# MB-Arduino-uno.net
KiCad netlist of a schematic drawn in EAGLE
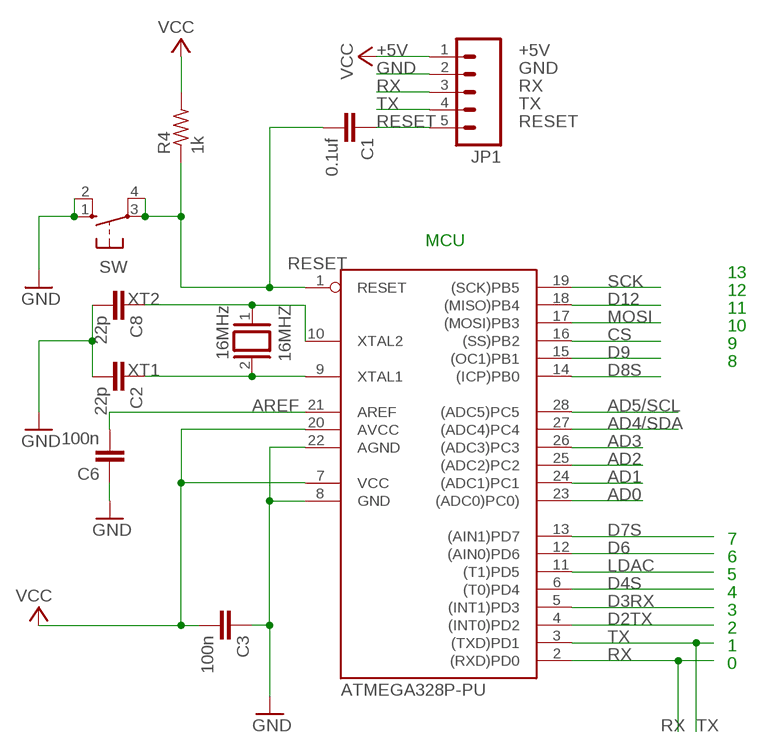
[diagram p0: schematic, sheet 1]

(export (version "E")
  (design (tool "Eeschema 10.0.6"))
  (components
    (comp (ref "16MHZ")
      (value "16MHz")
      (footprint "eagle-import:QS")
      (libsource (lib "eagle-import") (part "XTAL/S"))
    )
    (comp (ref "C1")
      (value "0.1uf")
      (footprint "eagle-import:C2.5-2")
      (libsource (lib "eagle-import") (part "C2.5/2"))
    )
    (comp (ref "C2")
      (value "22p")
      (footprint "eagle-import:C2.5-2")
      (libsource (lib "eagle-import") (part "C2.5/2"))
    )
    (comp (ref "C3")
      (value "100n")
      (footprint "eagle-import:C2.5-2")
      (libsource (lib "eagle-import") (part "C2.5/2"))
    )
    (comp (ref "C6")
      (value "100n")
      (footprint "eagle-import:C2.5-2")
      (libsource (lib "eagle-import") (part "C2.5/2"))
    )
    (comp (ref "C8")
      (value "22p")
      (footprint "eagle-import:C2.5-2")
      (libsource (lib "eagle-import") (part "C2.5/2"))
    )
    (comp (ref "IC")
      (value "ATMEGA328P-PU")
      (footprint "eagle-import:DIL28-3")
      (libsource (lib "eagle-import") (part "ATMEGA328P-PU"))
    )
    (comp (ref "JP1")
      (value "M05PTH")
      (footprint "eagle-import:1X05")
      (libsource (lib "eagle-import") (part "M05PTH"))
    )
    (comp (ref "R4")
      (value "1k")
      (footprint "eagle-import:0204_7")
      (libsource (lib "eagle-import") (part "R-US_0204/7"))
    )
    (comp (ref "SW")
      (value "10-XX")
      (footprint "eagle-import:B3F-10XX")
      (fields (field (name "MPN") "B3F-1000"))
      (libsource (lib "eagle-import") (part "10-XX"))
    )
  )
  (nets
    (net (code "1") (name "/AD0") (class "Default")
      (node (ref "IC") (pin "23") (pinfunction "(ADC0)PC0)_23") (pintype "bidirectional"))
    )
    (net (code "2") (name "/AD1") (class "Default")
      (node (ref "IC") (pin "24") (pinfunction "(ADC1)PC1_24") (pintype "bidirectional"))
    )
    (net (code "3") (name "/AD2") (class "Default")
      (node (ref "IC") (pin "25") (pinfunction "(ADC2)PC2_25") (pintype "bidirectional"))
    )
    (net (code "4") (name "/AD3") (class "Default")
      (node (ref "IC") (pin "26") (pinfunction "(ADC3)PC3_26") (pintype "bidirectional"))
    )
    (net (code "5") (name "/AD4{slash}SDA") (class "Default")
      (node (ref "IC") (pin "27") (pinfunction "(ADC4)PC4_27") (pintype "bidirectional"))
    )
    (net (code "6") (name "/AD5{slash}SCL") (class "Default")
      (node (ref "IC") (pin "28") (pinfunction "(ADC5)PC5_28") (pintype "bidirectional"))
    )
    (net (code "7") (name "/AREF") (class "Default")
      (node (ref "C6") (pin "2") (pinfunction "2_2") (pintype "passive"))
      (node (ref "IC") (pin "21") (pinfunction "AREF_21") (pintype "passive"))
    )
    (net (code "8") (name "/CS") (class "Default")
      (node (ref "IC") (pin "16") (pinfunction "(SS)PB2_16") (pintype "bidirectional"))
    )
    (net (code "9") (name "/D2TX") (class "Default")
      (node (ref "IC") (pin "4") (pinfunction "(INT0)PD2_4") (pintype "bidirectional"))
    )
    (net (code "10") (name "/D3RX") (class "Default")
      (node (ref "IC") (pin "5") (pinfunction "(INT1)PD3_5") (pintype "bidirectional"))
    )
    (net (code "11") (name "/D4S") (class "Default")
      (node (ref "IC") (pin "6") (pinfunction "(T0)PD4_6") (pintype "bidirectional"))
    )
    (net (code "12") (name "/D6") (class "Default")
      (node (ref "IC") (pin "12") (pinfunction "(AIN0)PD6_12") (pintype "bidirectional"))
    )
    (net (code "13") (name "/D7S") (class "Default")
      (node (ref "IC") (pin "13") (pinfunction "(AIN1)PD7_13") (pintype "bidirectional"))
    )
    (net (code "14") (name "/D8S") (class "Default")
      (node (ref "IC") (pin "14") (pinfunction "(ICP)PB0_14") (pintype "bidirectional"))
    )
    (net (code "15") (name "/D9") (class "Default")
      (node (ref "IC") (pin "15") (pinfunction "(OC1)PB1_15") (pintype "bidirectional"))
    )
    (net (code "16") (name "/D12") (class "Default")
      (node (ref "IC") (pin "18") (pinfunction "(MISO)PB4_18") (pintype "bidirectional"))
    )
    (net (code "17") (name "/LDAC") (class "Default")
      (node (ref "IC") (pin "11") (pinfunction "(T1)PD5_11") (pintype "bidirectional"))
    )
    (net (code "18") (name "/MOSI") (class "Default")
      (node (ref "IC") (pin "17") (pinfunction "(MOSI)PB3_17") (pintype "bidirectional"))
    )
    (net (code "19") (name "/RESET") (class "Default")
      (node (ref "C1") (pin "1") (pinfunction "1_1") (pintype "passive"))
      (node (ref "C1") (pin "2") (pinfunction "2_2") (pintype "passive"))
      (node (ref "IC") (pin "1") (pinfunction "RESET_1") (pintype "input"))
      (node (ref "JP1") (pin "5") (pinfunction "5_5") (pintype "passive"))
      (node (ref "R4") (pin "1") (pinfunction "1_1") (pintype "passive"))
      (node (ref "SW") (pin "3") (pinfunction "P_3") (pintype "passive"))
      (node (ref "SW") (pin "4") (pinfunction "P1_4") (pintype "passive"))
    )
    (net (code "20") (name "/RX") (class "Default")
      (node (ref "IC") (pin "2") (pinfunction "(RXD)PD0_2") (pintype "bidirectional"))
      (node (ref "JP1") (pin "3") (pinfunction "3_3") (pintype "passive"))
    )
    (net (code "21") (name "/SCK") (class "Default")
      (node (ref "IC") (pin "19") (pinfunction "(SCK)PB5_19") (pintype "bidirectional"))
    )
    (net (code "22") (name "/TX") (class "Default")
      (node (ref "IC") (pin "3") (pinfunction "(TXD)PD1_3") (pintype "bidirectional"))
      (node (ref "JP1") (pin "4") (pinfunction "4_4") (pintype "passive"))
    )
    (net (code "23") (name "/XT1") (class "Default")
      (node (ref "16MHZ") (pin "2") (pinfunction "2_2") (pintype "passive"))
      (node (ref "C2") (pin "1") (pinfunction "1_1") (pintype "passive"))
      (node (ref "IC") (pin "9") (pinfunction "XTAL1_9") (pintype "bidirectional"))
    )
    (net (code "24") (name "/XT2") (class "Default")
      (node (ref "16MHZ") (pin "1") (pinfunction "1_1") (pintype "passive"))
      (node (ref "C8") (pin "1") (pinfunction "1_1") (pintype "passive"))
      (node (ref "IC") (pin "10") (pinfunction "XTAL2_10") (pintype "bidirectional"))
    )
    (net (code "25") (name "GND") (class "Default")
      (node (ref "C2") (pin "2") (pinfunction "2_2") (pintype "passive"))
      (node (ref "C3") (pin "1") (pinfunction "1_1") (pintype "passive"))
      (node (ref "C6") (pin "1") (pinfunction "1_1") (pintype "passive"))
      (node (ref "C8") (pin "2") (pinfunction "2_2") (pintype "passive"))
      (node (ref "IC") (pin "22") (pinfunction "AGND_22") (pintype "power_in"))
      (node (ref "IC") (pin "8") (pinfunction "GND_8") (pintype "power_in"))
      (node (ref "JP1") (pin "2") (pinfunction "2_2") (pintype "passive"))
      (node (ref "SW") (pin "1") (pinfunction "S_1") (pintype "passive"))
      (node (ref "SW") (pin "2") (pinfunction "S1_2") (pintype "passive"))
    )
    (net (code "26") (name "VCC") (class "Default")
      (node (ref "C3") (pin "2") (pinfunction "2_2") (pintype "passive"))
      (node (ref "IC") (pin "20") (pinfunction "AVCC_20") (pintype "power_in"))
      (node (ref "IC") (pin "7") (pinfunction "VCC_7") (pintype "power_in"))
      (node (ref "JP1") (pin "1") (pinfunction "1_1") (pintype "passive"))
      (node (ref "R4") (pin "2") (pinfunction "2_2") (pintype "passive"))
    )
  )
)
